# audio-player-16bit.net
KiCad netlist of a schematic drawn in EAGLE
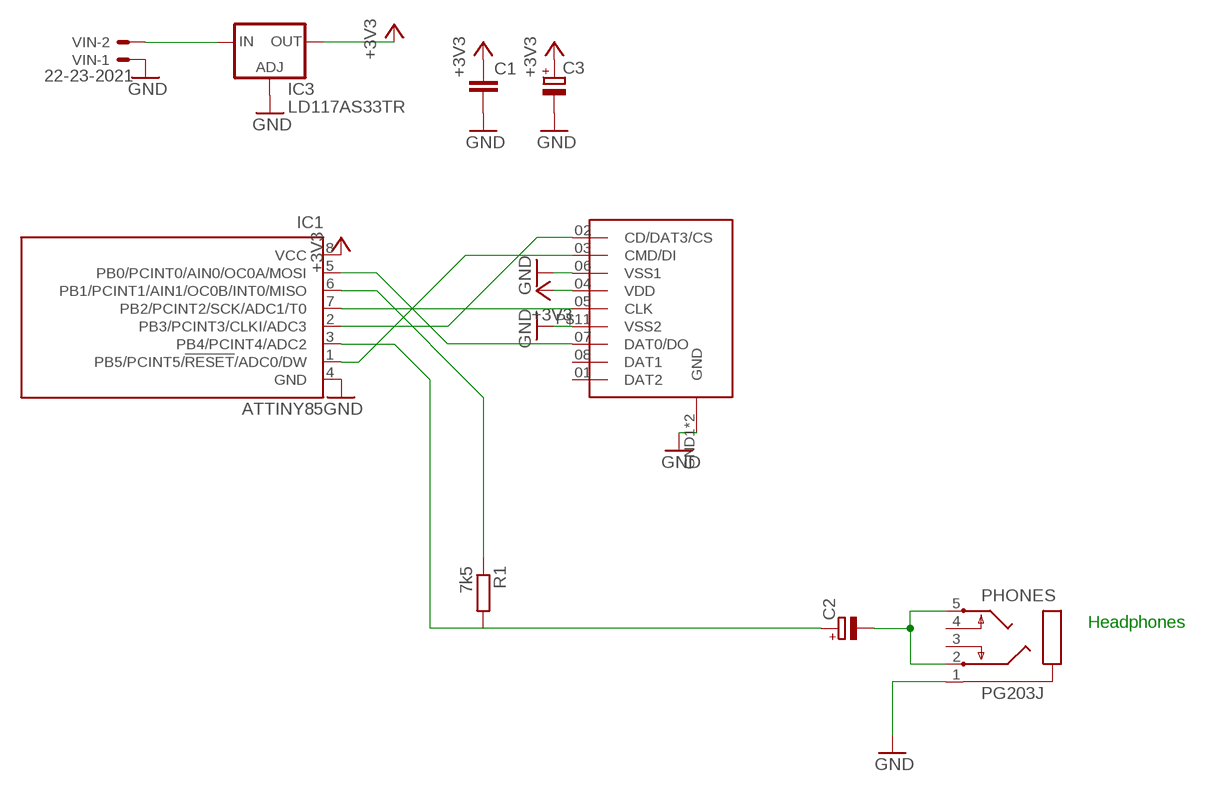
[diagram p0: schematic, sheet 1]

(export (version "E")
  (design (tool "Eeschema 10.0.6"))
  (components
    (comp (ref "C1")
      (value "C-EUC1206")
      (footprint "eagle-import:C1206")
      (libsource (lib "eagle-import") (part "C-EUC1206"))
    )
    (comp (ref "C2")
      (value "CPOL-EU140CLH-1014")
      (footprint "eagle-import:140CLH-1014")
      (libsource (lib "eagle-import") (part "CPOL-EU140CLH-1014"))
    )
    (comp (ref "C3")
      (value "CPOL-EUCT3528")
      (footprint "eagle-import:CT3528")
      (libsource (lib "eagle-import") (part "CPOL-EUCT3528"))
    )
    (comp (ref "IC1")
      (value "ATTINY85")
      (footprint "eagle-import:DIL08")
      (fields (field (name "MPN") "ATTINY13-20PU"))
      (libsource (lib "eagle-import") (part "TINY13PU-20"))
    )
    (comp (ref "IC3")
      (value "LD117AS33TR")
      (footprint "eagle-import:SOT223")
      (libsource (lib "eagle-import") (part "LD117A?S33TR"))
    )
    (comp (ref "PHONES")
      (value "PG203J")
      (footprint "eagle-import:PG203J")
      (libsource (lib "eagle-import") (part "PG203J"))
    )
    (comp (ref "R1")
      (value "7k5")
      (footprint "eagle-import:R1206")
      (libsource (lib "eagle-import") (part "R-EU_R1206"))
    )
    (comp (ref "U$1")
      (value "MICROSD")
      (footprint "eagle-import:SCHD3A0100")
      (libsource (lib "eagle-import") (part "MICROSD"))
    )
    (comp (ref "VIN")
      (value "22-23-2021")
      (footprint "eagle-import:22-23-2021")
      (fields (field (name "MF") "MOLEX"))
      (libsource (lib "eagle-import") (part "22-23-2021"))
    )
  )
  (nets
    (net (code "1") (name "+3V3") (class "Default")
      (node (ref "C1") (pin "1") (pinfunction "1_1") (pintype "passive"))
      (node (ref "C3") (pin "+") (pinfunction "+_+") (pintype "passive"))
      (node (ref "IC1") (pin "8") (pinfunction "VCC_8") (pintype "power_in"))
      (node (ref "IC3") (pin "4") (pinfunction "OUT_4") (pintype "passive"))
      (node (ref "U$1") (pin "04") (pinfunction "VDD_04") (pintype "bidirectional"))
    )
    (net (code "2") (name "GND") (class "Default")
      (node (ref "C1") (pin "2") (pinfunction "2_2") (pintype "passive"))
      (node (ref "C3") (pin "-") (pinfunction "-_-") (pintype "passive"))
      (node (ref "IC1") (pin "4") (pinfunction "GND_4") (pintype "power_in"))
      (node (ref "IC3") (pin "1") (pinfunction "ADJ_1") (pintype "input"))
      (node (ref "PHONES") (pin "1") (pinfunction "1_1") (pintype "passive"))
      (node (ref "U$1") (pin "06") (pinfunction "VSS1_06") (pintype "bidirectional"))
      (node (ref "U$1") (pin "GND1") (pinfunction "GND_GND1") (pintype "bidirectional"))
      (node (ref "U$1") (pin "GND2") (pinfunction "GND_GND2") (pintype "bidirectional"))
      (node (ref "U$1") (pin "P$11") (pinfunction "VSS2_P$11") (pintype "bidirectional"))
      (node (ref "VIN") (pin "1") (pinfunction "S_1") (pintype "passive"))
    )
    (net (code "3") (name "Net-(C2-Pad-)") (class "Default")
      (node (ref "C2") (pin "-") (pinfunction "-_-") (pintype "passive"))
      (node (ref "PHONES") (pin "2") (pinfunction "2_2") (pintype "passive"))
      (node (ref "PHONES") (pin "5") (pinfunction "5_5") (pintype "passive"))
    )
    (net (code "4") (name "Net-(IC1-PB0{slash}PCINT0{slash}AIN0{slash}OC0A{slash}MOSI)") (class "Default")
      (node (ref "IC1") (pin "5") (pinfunction "PB0/PCINT0/AIN0/OC0A/MOSI_5") (pintype "bidirectional"))
      (node (ref "U$1") (pin "07") (pinfunction "DAT0/DO_07") (pintype "bidirectional"))
    )
    (net (code "5") (name "Net-(IC1-PB1{slash}PCINT1{slash}AIN1{slash}OC0B{slash}INT0{slash}MISO)") (class "Default")
      (node (ref "IC1") (pin "6") (pinfunction "PB1/PCINT1/AIN1/OC0B/INT0/MISO_6") (pintype "bidirectional"))
      (node (ref "R1") (pin "1") (pinfunction "1_1") (pintype "passive"))
    )
    (net (code "6") (name "Net-(IC1-PB2{slash}PCINT2{slash}SCK{slash}ADC1{slash}T0)") (class "Default")
      (node (ref "IC1") (pin "7") (pinfunction "PB2/PCINT2/SCK/ADC1/T0_7") (pintype "bidirectional"))
      (node (ref "U$1") (pin "05") (pinfunction "CLK_05") (pintype "bidirectional"))
    )
    (net (code "7") (name "Net-(IC1-PB3{slash}PCINT3{slash}CLKI{slash}ADC3)") (class "Default")
      (node (ref "IC1") (pin "2") (pinfunction "PB3/PCINT3/CLKI/ADC3_2") (pintype "bidirectional"))
      (node (ref "U$1") (pin "02") (pinfunction "CD/DAT3/CS_02") (pintype "bidirectional"))
    )
    (net (code "8") (name "Net-(IC1-PB4{slash}PCINT4{slash}ADC2)") (class "Default")
      (node (ref "C2") (pin "+") (pinfunction "+_+") (pintype "passive"))
      (node (ref "IC1") (pin "3") (pinfunction "PB4/PCINT4/ADC2_3") (pintype "bidirectional"))
      (node (ref "R1") (pin "2") (pinfunction "2_2") (pintype "passive"))
    )
    (net (code "9") (name "Net-(IC1-PB5{slash}PCINT5{slash}~{RESET}{slash}ADC0{slash}DW)") (class "Default")
      (node (ref "IC1") (pin "1") (pinfunction "PB5/PCINT5/~{RESET}/ADC0/DW_1") (pintype "bidirectional"))
      (node (ref "U$1") (pin "03") (pinfunction "CMD/DI_03") (pintype "bidirectional"))
    )
    (net (code "10") (name "Net-(IC3-IN)") (class "Default")
      (node (ref "IC3") (pin "3") (pinfunction "IN_3") (pintype "input"))
      (node (ref "VIN") (pin "2") (pinfunction "S_2") (pintype "passive"))
    )
    (net (code "11") (name "unconnected-(PHONES-Pad3)") (class "Default")
      (node (ref "PHONES") (pin "3") (pinfunction "3_3") (pintype "passive"))
    )
    (net (code "12") (name "unconnected-(PHONES-Pad4)") (class "Default")
      (node (ref "PHONES") (pin "4") (pinfunction "4_4") (pintype "passive"))
    )
    (net (code "13") (name "unconnected-(U$1-DAT1-Pad08)") (class "Default")
      (node (ref "U$1") (pin "08") (pinfunction "DAT1_08") (pintype "bidirectional"))
    )
    (net (code "14") (name "unconnected-(U$1-DAT2-Pad01)") (class "Default")
      (node (ref "U$1") (pin "01") (pinfunction "DAT2_01") (pintype "bidirectional"))
    )
  )
)
